# Colin.net
KiCad netlist of a schematic drawn in Altium Designer
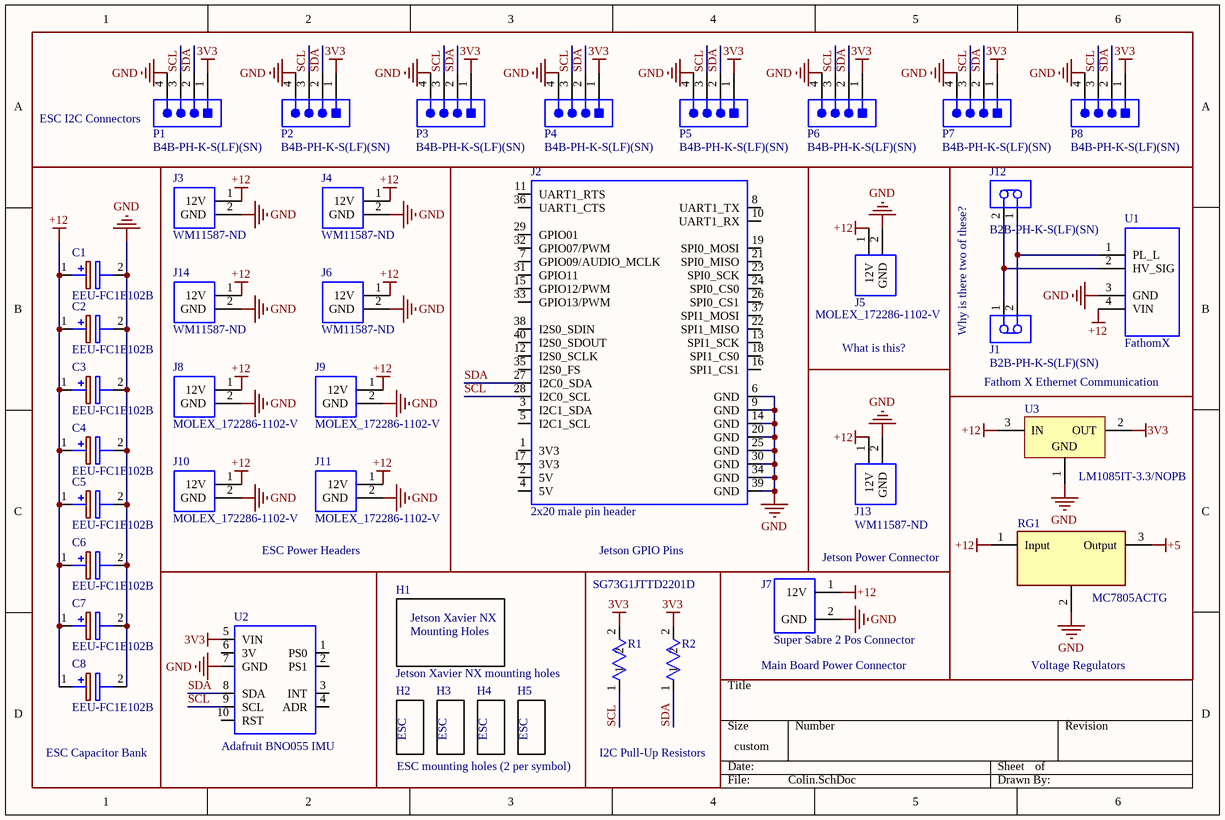
[diagram p0: Colin.SchDoc]

(export (version "E")
  (design (tool "Eeschema 10.0.6"))
  (components
    (comp (ref "C1")
      (value "EEU-FC1E102B")
      (footprint "EEU-FC1E102B")
      (libsource (lib "ColinSchLib") (part "EEU-FC1E102B"))
    )
    (comp (ref "C2")
      (value "EEU-FC1E102B")
      (footprint "EEU-FC1E102B")
      (libsource (lib "ColinSchLib") (part "EEU-FC1E102B"))
    )
    (comp (ref "C3")
      (value "EEU-FC1E102B")
      (footprint "EEU-FC1E102B")
      (libsource (lib "ColinSchLib") (part "EEU-FC1E102B"))
    )
    (comp (ref "C4")
      (value "EEU-FC1E102B")
      (footprint "EEU-FC1E102B")
      (libsource (lib "ColinSchLib") (part "EEU-FC1E102B"))
    )
    (comp (ref "C5")
      (value "EEU-FC1E102B")
      (footprint "EEU-FC1E102B")
      (libsource (lib "ColinSchLib") (part "EEU-FC1E102B"))
    )
    (comp (ref "C6")
      (value "EEU-FC1E102B")
      (footprint "EEU-FC1E102B")
      (libsource (lib "ColinSchLib") (part "EEU-FC1E102B"))
    )
    (comp (ref "C7")
      (value "EEU-FC1E102B")
      (footprint "EEU-FC1E102B")
      (libsource (lib "ColinSchLib") (part "EEU-FC1E102B"))
    )
    (comp (ref "C8")
      (value "EEU-FC1E102B")
      (footprint "EEU-FC1E102B")
      (libsource (lib "ColinSchLib") (part "EEU-FC1E102B"))
    )
    (comp (ref "H1")
      (value "Jetson Xavier NX mounting holes")
      (footprint "Jetson mounting holes")
      (libsource (lib "ColinSchLib") (part "Jetson Xavier NX mounting holes"))
    )
    (comp (ref "H2")
      (value "ESC mounting holes (2 per symbol)")
      (footprint "Jonathon ESC mounting holes")
      (libsource (lib "ColinSchLib") (part "ESC mounting holes"))
    )
    (comp (ref "H3")
      (value "ESC mounting holes")
      (footprint "Jonathon ESC mounting holes")
      (libsource (lib "ColinSchLib") (part "ESC mounting holes"))
    )
    (comp (ref "H4")
      (value "ESC mounting holes")
      (footprint "Jonathon ESC mounting holes")
      (libsource (lib "ColinSchLib") (part "ESC mounting holes"))
    )
    (comp (ref "H5")
      (value "ESC mounting holes")
      (footprint "Jonathon ESC mounting holes")
      (libsource (lib "ColinSchLib") (part "ESC mounting holes"))
    )
    (comp (ref "J1")
      (value "B2B-PH-K-S(LF)(SN)")
      (footprint "JST-B2B-PH-K-S_V")
      (fields (field (name "MANUFACTURER") "JST"))
      (libsource (lib "Altium Content Vault") (part "CN-2P-F-QF2"))
    )
    (comp (ref "J2")
      (value "2x20 male pin header")
      (footprint "2x20 pin header")
      (libsource (lib "ColinSchLib") (part "2x20 male pin header"))
    )
    (comp (ref "J3")
      (value "MOLEX_172310-1202-R/A")
      (footprint "2CONTAC_ULTRAFIT_R/A")
      (description "172310-1202. - CONNECTOR, HDR, 2POS, 1ROW, 3.5MM, R/A")
      (fields
        (field (name "MANUFACTURER") "Molex")
        (field (name "MANUFACTURER PART NUMBER") "172310-1202")
        (field (name "SUPPLIER PART NUMBER 1") "WM11587-ND")
      )
      (libsource (lib "ColinSchLib") (part "MOLEX_172310-1202-R/A"))
    )
    (comp (ref "J4")
      (value "MOLEX_172310-1202-R/A")
      (footprint "2CONTAC_ULTRAFIT_R/A")
      (description "172310-1202. - CONNECTOR, HDR, 2POS, 1ROW, 3.5MM, R/A")
      (fields
        (field (name "MANUFACTURER") "Molex")
        (field (name "MANUFACTURER PART NUMBER") "172310-1202")
        (field (name "SUPPLIER PART NUMBER 1") "WM11587-ND")
      )
      (libsource (lib "ColinSchLib") (part "MOLEX_172310-1202-R/A"))
    )
    (comp (ref "J5")
      (value "MOLEX_172286-1102-V")
      (footprint "Molex_172286-1102_0")
      (description "172286-1102, CONNECTOR, HEADER, 2POS, 1ROW, 3.5MM")
      (fields (field (name "MANUFACTURER") "Molex") (field (name "MANUFACTURER PART NUMBER") "172286-1102"))
      (libsource (lib "ColinSchLib") (part "MOLEX_172286-1102-V"))
    )
    (comp (ref "J6")
      (value "MOLEX_172310-1202-R/A")
      (footprint "2CONTAC_ULTRAFIT_R/A")
      (description "172310-1202. - CONNECTOR, HDR, 2POS, 1ROW, 3.5MM, R/A")
      (fields
        (field (name "MANUFACTURER") "Molex")
        (field (name "MANUFACTURER PART NUMBER") "172310-1202")
        (field (name "SUPPLIER PART NUMBER 1") "WM11587-ND")
      )
      (libsource (lib "ColinSchLib") (part "MOLEX_172310-1202-R/A"))
    )
    (comp (ref "J7")
      (value "Super Sabre 2 Pos Connector")
      (footprint "172043-0202")
      (libsource (lib "ColinSchLib") (part "Super Sabre 2 Pos Connector"))
    )
    (comp (ref "J8")
      (value "MOLEX_172286-1102-V")
      (footprint "Molex_172286-1102_0")
      (description "172286-1102, CONNECTOR, HEADER, 2POS, 1ROW, 3.5MM")
      (fields (field (name "MANUFACTURER") "Molex") (field (name "MANUFACTURER PART NUMBER") "172286-1102"))
      (libsource (lib "ColinSchLib") (part "MOLEX_172286-1102-V"))
    )
    (comp (ref "J9")
      (value "MOLEX_172286-1102-V")
      (footprint "Molex_172286-1102_0")
      (description "172286-1102, CONNECTOR, HEADER, 2POS, 1ROW, 3.5MM")
      (fields (field (name "MANUFACTURER") "Molex") (field (name "MANUFACTURER PART NUMBER") "172286-1102"))
      (libsource (lib "ColinSchLib") (part "MOLEX_172286-1102-V"))
    )
    (comp (ref "J10")
      (value "MOLEX_172286-1102-V")
      (footprint "Molex_172286-1102_0")
      (description "172286-1102, CONNECTOR, HEADER, 2POS, 1ROW, 3.5MM")
      (fields (field (name "MANUFACTURER") "Molex") (field (name "MANUFACTURER PART NUMBER") "172286-1102"))
      (libsource (lib "ColinSchLib") (part "MOLEX_172286-1102-V"))
    )
    (comp (ref "J11")
      (value "MOLEX_172286-1102-V")
      (footprint "Molex_172286-1102_0")
      (description "172286-1102, CONNECTOR, HEADER, 2POS, 1ROW, 3.5MM")
      (fields (field (name "MANUFACTURER") "Molex") (field (name "MANUFACTURER PART NUMBER") "172286-1102"))
      (libsource (lib "ColinSchLib") (part "MOLEX_172286-1102-V"))
    )
    (comp (ref "J12")
      (value "B2B-PH-K-S(LF)(SN)")
      (footprint "JST-B2B-PH-K-S_V")
      (fields (field (name "MANUFACTURER") "JST"))
      (libsource (lib "Altium Content Vault") (part "CN-2P-F-QF2"))
    )
    (comp (ref "J13")
      (value "MOLEX_172310-1202-R/A")
      (footprint "2CONTAC_ULTRAFIT_R/A")
      (description "172310-1202. - CONNECTOR, HDR, 2POS, 1ROW, 3.5MM, R/A")
      (fields
        (field (name "MANUFACTURER") "Molex")
        (field (name "MANUFACTURER PART NUMBER") "172310-1202")
        (field (name "SUPPLIER PART NUMBER 1") "WM11587-ND")
      )
      (libsource (lib "ColinSchLib") (part "MOLEX_172310-1202-R/A"))
    )
    (comp (ref "J14")
      (value "MOLEX_172310-1202-R/A")
      (footprint "2CONTAC_ULTRAFIT_R/A")
      (description "172310-1202. - CONNECTOR, HDR, 2POS, 1ROW, 3.5MM, R/A")
      (fields
        (field (name "MANUFACTURER") "Molex")
        (field (name "MANUFACTURER PART NUMBER") "172310-1202")
        (field (name "SUPPLIER PART NUMBER 1") "WM11587-ND")
      )
      (libsource (lib "ColinSchLib") (part "MOLEX_172310-1202-R/A"))
    )
    (comp (ref "P1")
      (value "B4B-PH-K-S(LF)(SN)")
      (footprint "JST-B4B-PH-K-S_V")
      (fields (field (name "MANUFACTURER") "JST"))
      (libsource (lib "Altium Content Vault") (part "CN-1P-M-R4"))
    )
    (comp (ref "P2")
      (value "B4B-PH-K-S(LF)(SN)")
      (footprint "JST-B4B-PH-K-S_V")
      (fields (field (name "MANUFACTURER") "JST"))
      (libsource (lib "Altium Content Vault") (part "CN-1P-M-R4"))
    )
    (comp (ref "P3")
      (value "B4B-PH-K-S(LF)(SN)")
      (footprint "JST-B4B-PH-K-S_V")
      (fields (field (name "MANUFACTURER") "JST"))
      (libsource (lib "Altium Content Vault") (part "CN-1P-M-R4"))
    )
    (comp (ref "P4")
      (value "B4B-PH-K-S(LF)(SN)")
      (footprint "JST-B4B-PH-K-S_V")
      (fields (field (name "MANUFACTURER") "JST"))
      (libsource (lib "Altium Content Vault") (part "CN-1P-M-R4"))
    )
    (comp (ref "P5")
      (value "B4B-PH-K-S(LF)(SN)")
      (footprint "JST-B4B-PH-K-S_V")
      (fields (field (name "MANUFACTURER") "JST"))
      (libsource (lib "Altium Content Vault") (part "CN-1P-M-R4"))
    )
    (comp (ref "P6")
      (value "B4B-PH-K-S(LF)(SN)")
      (footprint "JST-B4B-PH-K-S_V")
      (fields (field (name "MANUFACTURER") "JST"))
      (libsource (lib "Altium Content Vault") (part "CN-1P-M-R4"))
    )
    (comp (ref "P7")
      (value "B4B-PH-K-S(LF)(SN)")
      (footprint "JST-B4B-PH-K-S_V")
      (fields (field (name "MANUFACTURER") "JST"))
      (libsource (lib "Altium Content Vault") (part "CN-1P-M-R4"))
    )
    (comp (ref "P8")
      (value "B4B-PH-K-S(LF)(SN)")
      (footprint "JST-B4B-PH-K-S_V")
      (fields (field (name "MANUFACTURER") "JST"))
      (libsource (lib "Altium Content Vault") (part "CN-1P-M-R4"))
    )
    (comp (ref "R1")
      (value "SG73G1JTTD2201D")
      (footprint "SG73G1JTTD2201D")
      (description "Res Thick Film 0603 2.2K Ohm 0.5% 0.33W(1/3W) ±50ppm/°C Pad SMD Automotive T/R")
      (fields
        (field (name "MANUFACTURER") "KOA Speer")
        (field (name "SUPPLIER PART NUMBER 1") "SG73G1JTTD2201D")
      )
      (libsource (lib "ColinSchLib") (part "SG73G1JTTD2201D"))
    )
    (comp (ref "R2")
      (value "SG73G1JTTD2201D")
      (footprint "SG73G1JTTD2201D")
      (description "Res Thick Film 0603 2.2K Ohm 0.5% 0.33W(1/3W) ±50ppm/°C Pad SMD Automotive T/R")
      (fields (field (name "MANUFACTURER") "KOA Speer"))
      (libsource (lib "ColinSchLib") (part "SG73G1JTTD2201D"))
    )
    (comp (ref "RG1")
      (value "Reg_ON_Semi_MC7805ACTG_eec")
      (footprint "ON_Semi_221AB_0")
      (description "REG IC REG LDO 5V 1A TO220AB")
      (fields
        (field (name "VOLTAGE") "5V")
        (field (name "MANUFACTURER") "ON Semi")
        (field (name "PART NUMBER") "MC7805ACTG")
      )
      (libsource (lib "ColinSchLib") (part "Reg_ON_Semi_MC7805ACTG_eec"))
    )
    (comp (ref "U1")
      (value "FathomX")
      (footprint "FATHOM-X")
      (libsource (lib "ColinSchLib") (part "FathomX"))
    )
    (comp (ref "U2")
      (value "Adafruit BNO055 IMU")
      (footprint "Adafruit BNO055 IMU")
      (libsource (lib "ColinSchLib") (part "Adafruit BNO055 IMU"))
    )
    (comp (ref "U3")
      (value "LM1085IT-3.3/NOPB")
      (footprint "NDE0003A")
      (description "3A Low Dropout Positive Regulators, 3-pin TO-220, Pb-Free")
      (fields (field (name "MANUFACTURER") "Texas Instruments"))
      (libsource (lib "Altium Content Vault") (part "PM-REG-LM1086-SIL3"))
    )
  )
  (nets
    (net (code "1") (name "+5") (class "Default")
      (node (ref "RG1") (pin "3") (pinfunction "Output_3") (pintype "passive"))
    )
    (net (code "2") (name "+12") (class "Default")
      (node (ref "C1") (pin "1") (pinfunction "+_1") (pintype "passive"))
      (node (ref "C2") (pin "1") (pinfunction "+_1") (pintype "passive"))
      (node (ref "C3") (pin "1") (pinfunction "+_1") (pintype "passive"))
      (node (ref "C4") (pin "1") (pinfunction "+_1") (pintype "passive"))
      (node (ref "C5") (pin "1") (pinfunction "+_1") (pintype "passive"))
      (node (ref "C6") (pin "1") (pinfunction "+_1") (pintype "passive"))
      (node (ref "C7") (pin "1") (pinfunction "+_1") (pintype "passive"))
      (node (ref "C8") (pin "1") (pinfunction "+_1") (pintype "passive"))
      (node (ref "J10") (pin "1") (pinfunction "12V_1") (pintype "passive"))
      (node (ref "J11") (pin "1") (pinfunction "12V_1") (pintype "passive"))
      (node (ref "J13") (pin "1") (pinfunction "12V_1") (pintype "passive"))
      (node (ref "J14") (pin "1") (pinfunction "12V_1") (pintype "passive"))
      (node (ref "J3") (pin "1") (pinfunction "12V_1") (pintype "passive"))
      (node (ref "J4") (pin "1") (pinfunction "12V_1") (pintype "passive"))
      (node (ref "J5") (pin "1") (pinfunction "12V_1") (pintype "passive"))
      (node (ref "J6") (pin "1") (pinfunction "12V_1") (pintype "passive"))
      (node (ref "J7") (pin "1") (pinfunction "12V_1") (pintype "passive"))
      (node (ref "J8") (pin "1") (pinfunction "12V_1") (pintype "passive"))
      (node (ref "J9") (pin "1") (pinfunction "12V_1") (pintype "passive"))
      (node (ref "RG1") (pin "1") (pinfunction "Input_1") (pintype "passive"))
      (node (ref "U1") (pin "4") (pinfunction "VIN_4") (pintype "passive"))
      (node (ref "U3") (pin "3") (pinfunction "IN_3") (pintype "power_in"))
    )
    (net (code "3") (name "/SCL") (class "Default")
      (node (ref "J2") (pin "28") (pinfunction "I2C0_SCL_28") (pintype "passive"))
      (node (ref "P1") (pin "3") (pinfunction "3_3") (pintype "passive"))
      (node (ref "P2") (pin "3") (pinfunction "3_3") (pintype "passive"))
      (node (ref "P3") (pin "3") (pinfunction "3_3") (pintype "passive"))
      (node (ref "P4") (pin "3") (pinfunction "3_3") (pintype "passive"))
      (node (ref "P5") (pin "3") (pinfunction "3_3") (pintype "passive"))
      (node (ref "P6") (pin "3") (pinfunction "3_3") (pintype "passive"))
      (node (ref "P7") (pin "3") (pinfunction "3_3") (pintype "passive"))
      (node (ref "P8") (pin "3") (pinfunction "3_3") (pintype "passive"))
      (node (ref "R1") (pin "1") (pinfunction "1_1") (pintype "passive"))
      (node (ref "U2") (pin "9") (pinfunction "SCL_9") (pintype "passive"))
    )
    (net (code "4") (name "/SDA") (class "Default")
      (node (ref "J2") (pin "27") (pinfunction "I2C0_SDA_27") (pintype "passive"))
      (node (ref "P1") (pin "2") (pinfunction "2_2") (pintype "passive"))
      (node (ref "P2") (pin "2") (pinfunction "2_2") (pintype "passive"))
      (node (ref "P3") (pin "2") (pinfunction "2_2") (pintype "passive"))
      (node (ref "P4") (pin "2") (pinfunction "2_2") (pintype "passive"))
      (node (ref "P5") (pin "2") (pinfunction "2_2") (pintype "passive"))
      (node (ref "P6") (pin "2") (pinfunction "2_2") (pintype "passive"))
      (node (ref "P7") (pin "2") (pinfunction "2_2") (pintype "passive"))
      (node (ref "P8") (pin "2") (pinfunction "2_2") (pintype "passive"))
      (node (ref "R2") (pin "1") (pinfunction "1_1") (pintype "passive"))
      (node (ref "U2") (pin "8") (pinfunction "SDA_8") (pintype "passive"))
    )
    (net (code "5") (name "3V3") (class "Default")
      (node (ref "P1") (pin "1") (pinfunction "1_1") (pintype "passive"))
      (node (ref "P2") (pin "1") (pinfunction "1_1") (pintype "passive"))
      (node (ref "P3") (pin "1") (pinfunction "1_1") (pintype "passive"))
      (node (ref "P4") (pin "1") (pinfunction "1_1") (pintype "passive"))
      (node (ref "P5") (pin "1") (pinfunction "1_1") (pintype "passive"))
      (node (ref "P6") (pin "1") (pinfunction "1_1") (pintype "passive"))
      (node (ref "P7") (pin "1") (pinfunction "1_1") (pintype "passive"))
      (node (ref "P8") (pin "1") (pinfunction "1_1") (pintype "passive"))
      (node (ref "R1") (pin "2") (pinfunction "2_2") (pintype "passive"))
      (node (ref "R2") (pin "2") (pinfunction "2_2") (pintype "passive"))
      (node (ref "U2") (pin "5") (pinfunction "VIN_5") (pintype "passive"))
      (node (ref "U3") (pin "2") (pinfunction "OUT_2") (pintype "power_in"))
    )
    (net (code "6") (name "GND") (class "Default")
      (node (ref "C1") (pin "2") (pinfunction "-_2") (pintype "passive"))
      (node (ref "C2") (pin "2") (pinfunction "-_2") (pintype "passive"))
      (node (ref "C3") (pin "2") (pinfunction "-_2") (pintype "passive"))
      (node (ref "C4") (pin "2") (pinfunction "-_2") (pintype "passive"))
      (node (ref "C5") (pin "2") (pinfunction "-_2") (pintype "passive"))
      (node (ref "C6") (pin "2") (pinfunction "-_2") (pintype "passive"))
      (node (ref "C7") (pin "2") (pinfunction "-_2") (pintype "passive"))
      (node (ref "C8") (pin "2") (pinfunction "-_2") (pintype "passive"))
      (node (ref "J10") (pin "2") (pinfunction "GND_2") (pintype "passive"))
      (node (ref "J11") (pin "2") (pinfunction "GND_2") (pintype "passive"))
      (node (ref "J13") (pin "2") (pinfunction "GND_2") (pintype "passive"))
      (node (ref "J14") (pin "2") (pinfunction "GND_2") (pintype "passive"))
      (node (ref "J2") (pin "14") (pinfunction "GND_14") (pintype "passive"))
      (node (ref "J2") (pin "20") (pinfunction "GND_20") (pintype "passive"))
      (node (ref "J2") (pin "25") (pinfunction "GND_25") (pintype "passive"))
      (node (ref "J2") (pin "30") (pinfunction "GND_30") (pintype "passive"))
      (node (ref "J2") (pin "34") (pinfunction "GND_34") (pintype "passive"))
      (node (ref "J2") (pin "39") (pinfunction "GND_39") (pintype "passive"))
      (node (ref "J2") (pin "6") (pinfunction "GND_6") (pintype "passive"))
      (node (ref "J2") (pin "9") (pinfunction "GND_9") (pintype "passive"))
      (node (ref "J3") (pin "2") (pinfunction "GND_2") (pintype "passive"))
      (node (ref "J4") (pin "2") (pinfunction "GND_2") (pintype "passive"))
      (node (ref "J5") (pin "2") (pinfunction "GND_2") (pintype "passive"))
      (node (ref "J6") (pin "2") (pinfunction "GND_2") (pintype "passive"))
      (node (ref "J7") (pin "2") (pinfunction "GND_2") (pintype "passive"))
      (node (ref "J8") (pin "2") (pinfunction "GND_2") (pintype "passive"))
      (node (ref "J9") (pin "2") (pinfunction "GND_2") (pintype "passive"))
      (node (ref "P1") (pin "4") (pinfunction "4_4") (pintype "passive"))
      (node (ref "P2") (pin "4") (pinfunction "4_4") (pintype "passive"))
      (node (ref "P3") (pin "4") (pinfunction "4_4") (pintype "passive"))
      (node (ref "P4") (pin "4") (pinfunction "4_4") (pintype "passive"))
      (node (ref "P5") (pin "4") (pinfunction "4_4") (pintype "passive"))
      (node (ref "P6") (pin "4") (pinfunction "4_4") (pintype "passive"))
      (node (ref "P7") (pin "4") (pinfunction "4_4") (pintype "passive"))
      (node (ref "P8") (pin "4") (pinfunction "4_4") (pintype "passive"))
      (node (ref "RG1") (pin "2") (pinfunction "Ground_2") (pintype "passive"))
      (node (ref "U1") (pin "3") (pinfunction "GND_3") (pintype "passive"))
      (node (ref "U2") (pin "7") (pinfunction "GND_7") (pintype "passive"))
      (node (ref "U3") (pin "1") (pinfunction "GND_1") (pintype "power_in"))
    )
    (net (code "7") (name "Net-(U1-HV_SIG)") (class "Default")
      (node (ref "J1") (pin "1") (pinfunction "1_1") (pintype "passive"))
      (node (ref "J12") (pin "2") (pinfunction "2_2") (pintype "passive"))
      (node (ref "U1") (pin "2") (pinfunction "HV_SIG_2") (pintype "passive"))
    )
    (net (code "8") (name "Net-(U1-PL_L)") (class "Default")
      (node (ref "J1") (pin "2") (pinfunction "2_2") (pintype "passive"))
      (node (ref "J12") (pin "1") (pinfunction "1_1") (pintype "passive"))
      (node (ref "U1") (pin "1") (pinfunction "PL_L_1") (pintype "passive"))
    )
    (net (code "9") (name "unconnected-(J2-3V3-Pad1)") (class "Default")
      (node (ref "J2") (pin "1") (pinfunction "3V3_1") (pintype "passive"))
    )
    (net (code "10") (name "unconnected-(J2-3V3-Pad17)") (class "Default")
      (node (ref "J2") (pin "17") (pinfunction "3V3_17") (pintype "passive"))
    )
    (net (code "11") (name "unconnected-(J2-5V-Pad2)") (class "Default")
      (node (ref "J2") (pin "2") (pinfunction "5V_2") (pintype "passive"))
    )
    (net (code "12") (name "unconnected-(J2-5V-Pad4)") (class "Default")
      (node (ref "J2") (pin "4") (pinfunction "5V_4") (pintype "passive"))
    )
    (net (code "13") (name "unconnected-(J2-GPIO01-Pad29)") (class "Default")
      (node (ref "J2") (pin "29") (pinfunction "GPIO01_29") (pintype "passive"))
    )
    (net (code "14") (name "unconnected-(J2-GPIO07{slash}PWM-Pad32)") (class "Default")
      (node (ref "J2") (pin "32") (pinfunction "GPIO07/PWM_32") (pintype "passive"))
    )
    (net (code "15") (name "unconnected-(J2-GPIO09{slash}AUDIO_MCLK-Pad7)") (class "Default")
      (node (ref "J2") (pin "7") (pinfunction "GPIO09/AUDIO_MCLK_7") (pintype "passive"))
    )
    (net (code "16") (name "unconnected-(J2-GPIO11-Pad31)") (class "Default")
      (node (ref "J2") (pin "31") (pinfunction "GPIO11_31") (pintype "passive"))
    )
    (net (code "17") (name "unconnected-(J2-GPIO12{slash}PWM-Pad15)") (class "Default")
      (node (ref "J2") (pin "15") (pinfunction "GPIO12/PWM_15") (pintype "passive"))
    )
    (net (code "18") (name "unconnected-(J2-GPIO13{slash}PWM-Pad33)") (class "Default")
      (node (ref "J2") (pin "33") (pinfunction "GPIO13/PWM_33") (pintype "passive"))
    )
    (net (code "19") (name "unconnected-(J2-I2C1_SCL-Pad5)") (class "Default")
      (node (ref "J2") (pin "5") (pinfunction "I2C1_SCL_5") (pintype "passive"))
    )
    (net (code "20") (name "unconnected-(J2-I2C1_SDA-Pad3)") (class "Default")
      (node (ref "J2") (pin "3") (pinfunction "I2C1_SDA_3") (pintype "passive"))
    )
    (net (code "21") (name "unconnected-(J2-I2S0_FS-Pad35)") (class "Default")
      (node (ref "J2") (pin "35") (pinfunction "I2S0_FS_35") (pintype "passive"))
    )
    (net (code "22") (name "unconnected-(J2-I2S0_SCLK-Pad12)") (class "Default")
      (node (ref "J2") (pin "12") (pinfunction "I2S0_SCLK_12") (pintype "passive"))
    )
    (net (code "23") (name "unconnected-(J2-I2S0_SDIN-Pad38)") (class "Default")
      (node (ref "J2") (pin "38") (pinfunction "I2S0_SDIN_38") (pintype "passive"))
    )
    (net (code "24") (name "unconnected-(J2-I2S0_SDOUT-Pad40)") (class "Default")
      (node (ref "J2") (pin "40") (pinfunction "I2S0_SDOUT_40") (pintype "passive"))
    )
    (net (code "25") (name "unconnected-(J2-SPI0_CS0-Pad24)") (class "Default")
      (node (ref "J2") (pin "24") (pinfunction "SPI0_CS0_24") (pintype "passive"))
    )
    (net (code "26") (name "unconnected-(J2-SPI0_CS1-Pad26)") (class "Default")
      (node (ref "J2") (pin "26") (pinfunction "SPI0_CS1_26") (pintype "passive"))
    )
    (net (code "27") (name "unconnected-(J2-SPI0_MISO-Pad21)") (class "Default")
      (node (ref "J2") (pin "21") (pinfunction "SPI0_MISO_21") (pintype "passive"))
    )
    (net (code "28") (name "unconnected-(J2-SPI0_MOSI-Pad19)") (class "Default")
      (node (ref "J2") (pin "19") (pinfunction "SPI0_MOSI_19") (pintype "passive"))
    )
    (net (code "29") (name "unconnected-(J2-SPI0_SCK-Pad23)") (class "Default")
      (node (ref "J2") (pin "23") (pinfunction "SPI0_SCK_23") (pintype "passive"))
    )
    (net (code "30") (name "unconnected-(J2-SPI1_CS0-Pad18)") (class "Default")
      (node (ref "J2") (pin "18") (pinfunction "SPI1_CS0_18") (pintype "passive"))
    )
    (net (code "31") (name "unconnected-(J2-SPI1_CS1-Pad16)") (class "Default")
      (node (ref "J2") (pin "16") (pinfunction "SPI1_CS1_16") (pintype "passive"))
    )
    (net (code "32") (name "unconnected-(J2-SPI1_MISO-Pad22)") (class "Default")
      (node (ref "J2") (pin "22") (pinfunction "SPI1_MISO_22") (pintype "passive"))
    )
    (net (code "33") (name "unconnected-(J2-SPI1_MOSI-Pad37)") (class "Default")
      (node (ref "J2") (pin "37") (pinfunction "SPI1_MOSI_37") (pintype "passive"))
    )
    (net (code "34") (name "unconnected-(J2-SPI1_SCK-Pad13)") (class "Default")
      (node (ref "J2") (pin "13") (pinfunction "SPI1_SCK_13") (pintype "passive"))
    )
    (net (code "35") (name "unconnected-(J2-UART1_CTS-Pad36)") (class "Default")
      (node (ref "J2") (pin "36") (pinfunction "UART1_CTS_36") (pintype "passive"))
    )
    (net (code "36") (name "unconnected-(J2-UART1_RTS-Pad11)") (class "Default")
      (node (ref "J2") (pin "11") (pinfunction "UART1_RTS_11") (pintype "passive"))
    )
    (net (code "37") (name "unconnected-(J2-UART1_RX-Pad10)") (class "Default")
      (node (ref "J2") (pin "10") (pinfunction "UART1_RX_10") (pintype "passive"))
    )
    (net (code "38") (name "unconnected-(J2-UART1_TX-Pad8)") (class "Default")
      (node (ref "J2") (pin "8") (pinfunction "UART1_TX_8") (pintype "passive"))
    )
    (net (code "39") (name "unconnected-(U2-3V-Pad6)") (class "Default")
      (node (ref "U2") (pin "6") (pinfunction "3V_6") (pintype "passive"))
    )
    (net (code "40") (name "unconnected-(U2-ADR-Pad4)") (class "Default")
      (node (ref "U2") (pin "4") (pinfunction "ADR_4") (pintype "passive"))
    )
    (net (code "41") (name "unconnected-(U2-INT-Pad3)") (class "Default")
      (node (ref "U2") (pin "3") (pinfunction "INT_3") (pintype "passive"))
    )
    (net (code "42") (name "unconnected-(U2-PS0-Pad1)") (class "Default")
      (node (ref "U2") (pin "1") (pinfunction "PS0_1") (pintype "passive"))
    )
    (net (code "43") (name "unconnected-(U2-PS1-Pad2)") (class "Default")
      (node (ref "U2") (pin "2") (pinfunction "PS1_2") (pintype "passive"))
    )
    (net (code "44") (name "unconnected-(U2-RST-Pad10)") (class "Default")
      (node (ref "U2") (pin "10") (pinfunction "RST_10") (pintype "passive"))
    )
  )
)
